# testv1.net
KiCad netlist of a schematic drawn in EAGLE
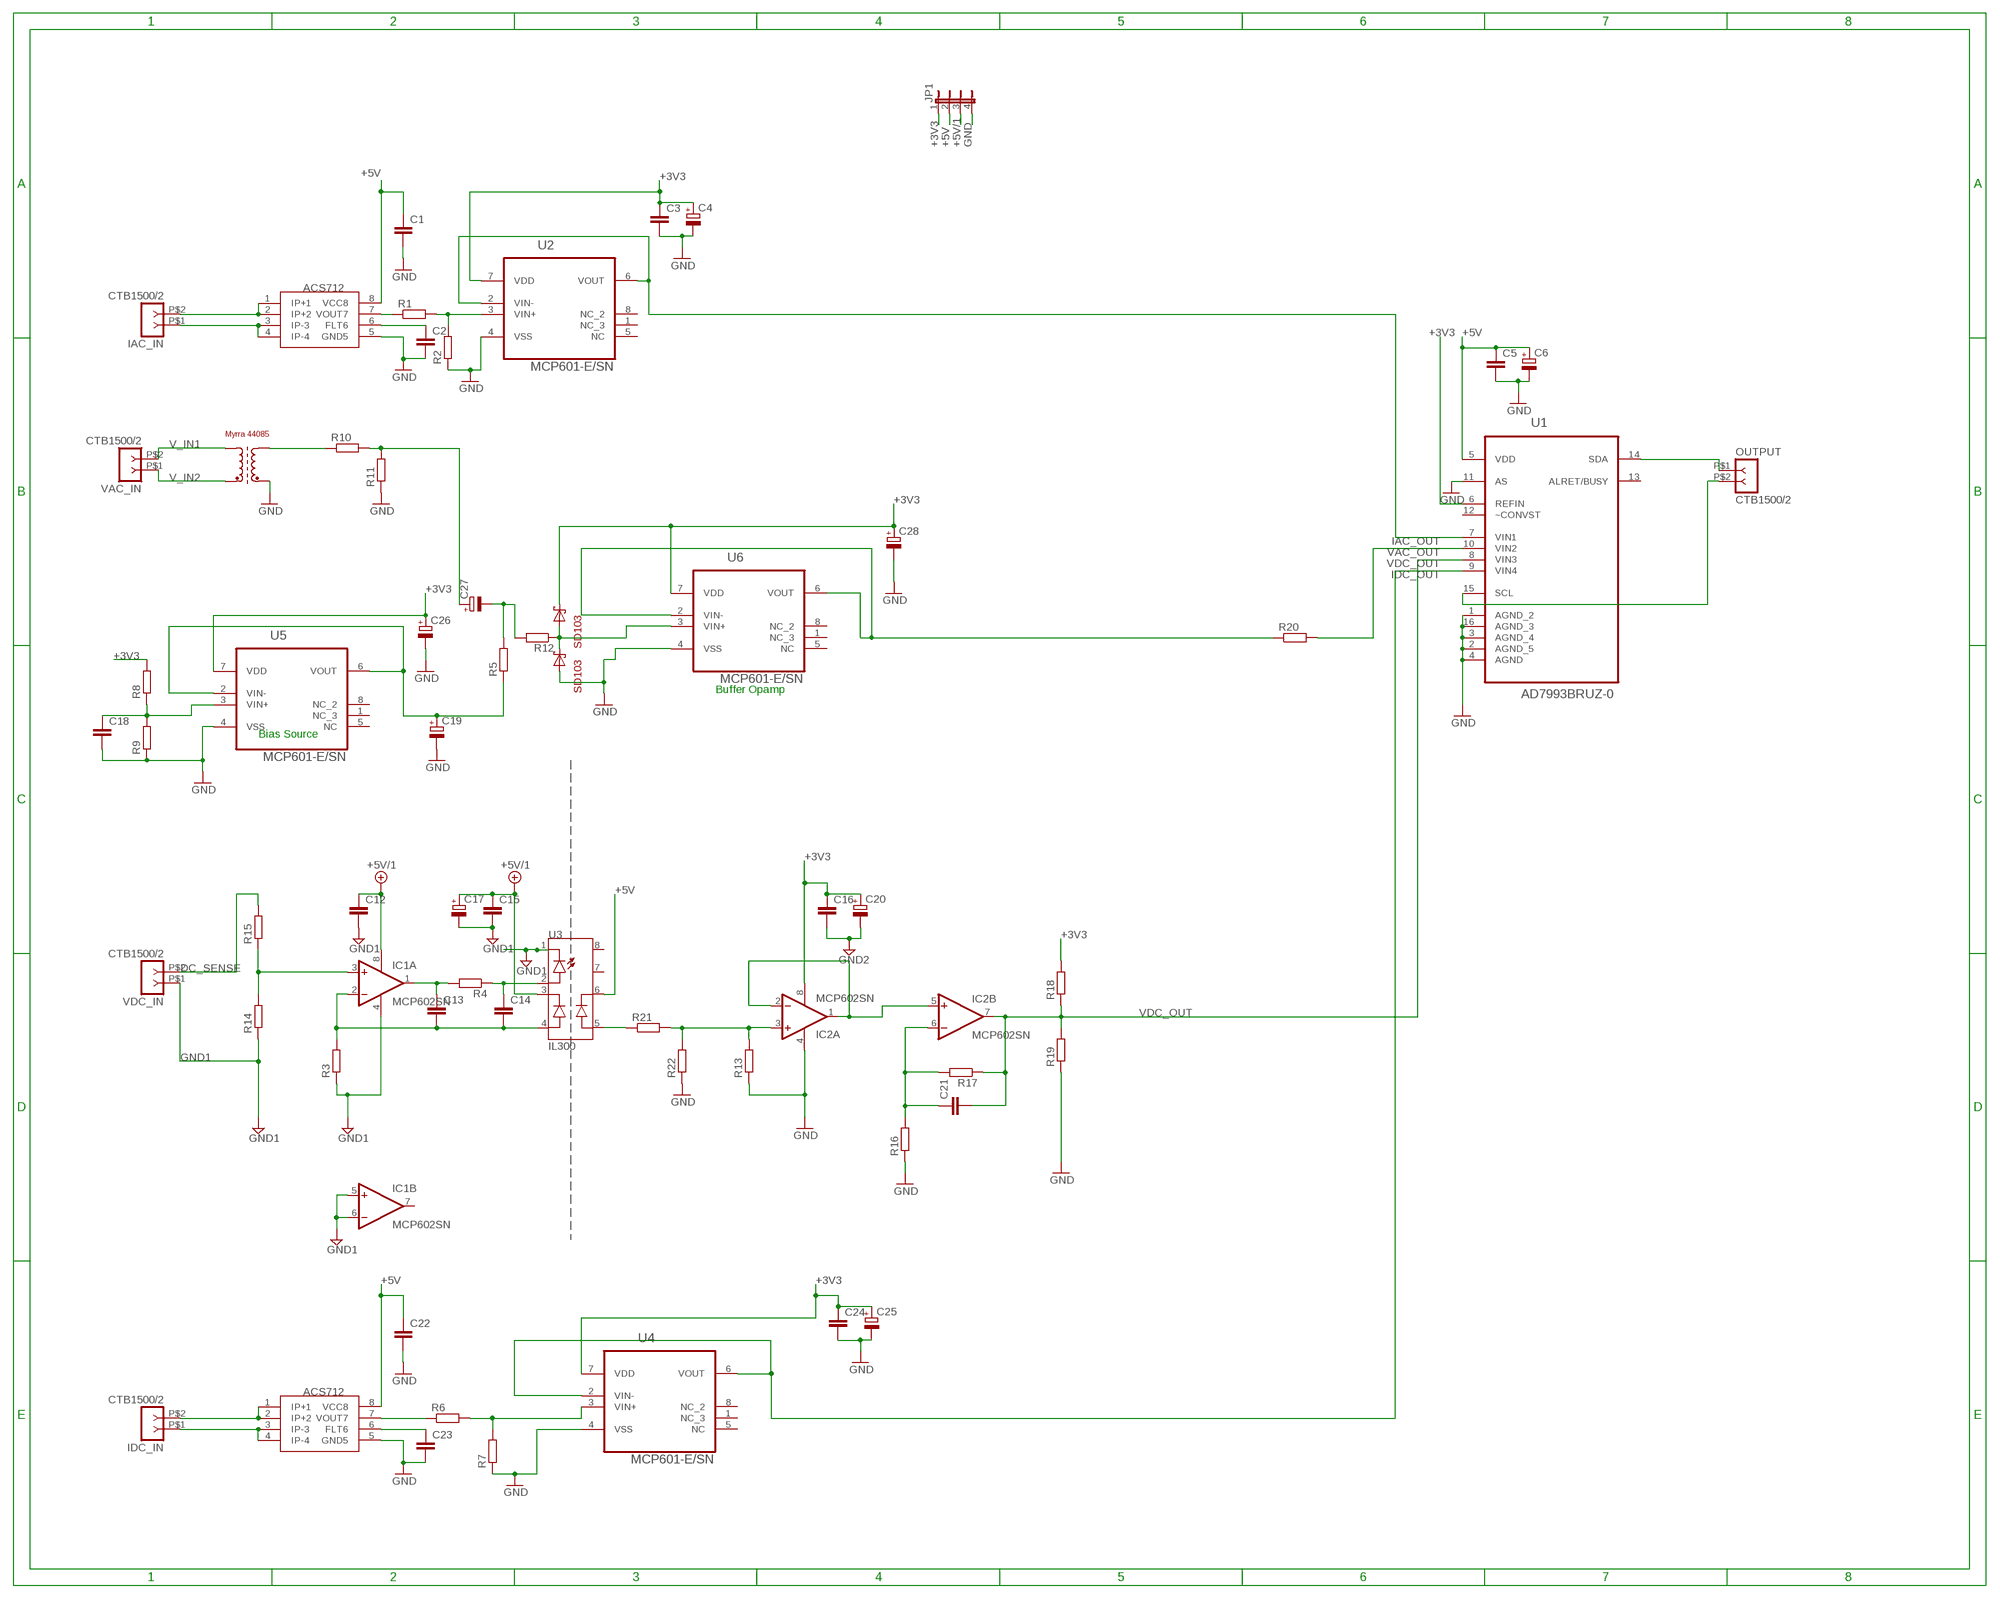
[diagram p0: schematic, sheet 1]

(export (version "E")
  (design (tool "Eeschema 10.0.6"))
  (components
    (comp (ref "C1")
      (value "C-EU025-025X050")
      (footprint "eagle-import:C025-025X050")
      (libsource (lib "eagle-import") (part "C-EU025-025X050"))
    )
    (comp (ref "C2")
      (value "C-EU025-025X050")
      (footprint "eagle-import:C025-025X050")
      (libsource (lib "eagle-import") (part "C-EU025-025X050"))
    )
    (comp (ref "C3")
      (value "C-EU025-025X050")
      (footprint "eagle-import:C025-025X050")
      (libsource (lib "eagle-import") (part "C-EU025-025X050"))
    )
    (comp (ref "C4")
      (value "CPOL-EUE2-4")
      (footprint "eagle-import:E2-4")
      (libsource (lib "eagle-import") (part "CPOL-EUE2-4"))
    )
    (comp (ref "C5")
      (value "C-EU025-025X050")
      (footprint "eagle-import:C025-025X050")
      (libsource (lib "eagle-import") (part "C-EU025-025X050"))
    )
    (comp (ref "C6")
      (value "CPOL-EUE2-4")
      (footprint "eagle-import:E2-4")
      (libsource (lib "eagle-import") (part "CPOL-EUE2-4"))
    )
    (comp (ref "C12")
      (value "C-EU025-025X050")
      (footprint "eagle-import:C025-025X050")
      (libsource (lib "eagle-import") (part "C-EU025-025X050"))
    )
    (comp (ref "C13")
      (value "C-EU025-025X050")
      (footprint "eagle-import:C025-025X050")
      (libsource (lib "eagle-import") (part "C-EU025-025X050"))
    )
    (comp (ref "C14")
      (value "C-EU025-025X050")
      (footprint "eagle-import:C025-025X050")
      (libsource (lib "eagle-import") (part "C-EU025-025X050"))
    )
    (comp (ref "C15")
      (value "C-EU025-025X050")
      (footprint "eagle-import:C025-025X050")
      (libsource (lib "eagle-import") (part "C-EU025-025X050"))
    )
    (comp (ref "C16")
      (value "C-EU025-025X050")
      (footprint "eagle-import:C025-025X050")
      (libsource (lib "eagle-import") (part "C-EU025-025X050"))
    )
    (comp (ref "C17")
      (value "CPOL-EUE2-4")
      (footprint "eagle-import:E2-4")
      (libsource (lib "eagle-import") (part "CPOL-EUE2-4"))
    )
    (comp (ref "C18")
      (value "C-EU025-025X050")
      (footprint "eagle-import:C025-025X050")
      (libsource (lib "eagle-import") (part "C-EU025-025X050"))
    )
    (comp (ref "C19")
      (value "CPOL-EUE2-4")
      (footprint "eagle-import:E2-4")
      (libsource (lib "eagle-import") (part "CPOL-EUE2-4"))
    )
    (comp (ref "C20")
      (value "CPOL-EUE2-4")
      (footprint "eagle-import:E2-4")
      (libsource (lib "eagle-import") (part "CPOL-EUE2-4"))
    )
    (comp (ref "C21")
      (value "C-EU025-025X050")
      (footprint "eagle-import:C025-025X050")
      (libsource (lib "eagle-import") (part "C-EU025-025X050"))
    )
    (comp (ref "C22")
      (value "C-EU025-025X050")
      (footprint "eagle-import:C025-025X050")
      (libsource (lib "eagle-import") (part "C-EU025-025X050"))
    )
    (comp (ref "C23")
      (value "C-EU025-025X050")
      (footprint "eagle-import:C025-025X050")
      (libsource (lib "eagle-import") (part "C-EU025-025X050"))
    )
    (comp (ref "C24")
      (value "C-EU025-025X050")
      (footprint "eagle-import:C025-025X050")
      (libsource (lib "eagle-import") (part "C-EU025-025X050"))
    )
    (comp (ref "C25")
      (value "CPOL-EUE2-4")
      (footprint "eagle-import:E2-4")
      (libsource (lib "eagle-import") (part "CPOL-EUE2-4"))
    )
    (comp (ref "C26")
      (value "CPOL-EUE2-4")
      (footprint "eagle-import:E2-4")
      (libsource (lib "eagle-import") (part "CPOL-EUE2-4"))
    )
    (comp (ref "C27")
      (value "CPOL-EUE2-4")
      (footprint "eagle-import:E2-4")
      (libsource (lib "eagle-import") (part "CPOL-EUE2-4"))
    )
    (comp (ref "C28")
      (value "CPOL-EUE2-4")
      (footprint "eagle-import:E2-4")
      (libsource (lib "eagle-import") (part "CPOL-EUE2-4"))
    )
    (comp (ref "IAC_IN")
      (value "CTB1500/2")
      (footprint "eagle-import:CTB1500-2")
      (libsource (lib "eagle-import") (part "CTB1500/2"))
    )
    (comp (ref "IC1")
      (value "MCP602SN")
      (footprint "eagle-import:SO08")
      (libsource (lib "eagle-import") (part "MCP602SN"))
    )
    (comp (ref "IC2")
      (value "MCP602SN")
      (footprint "eagle-import:SO08")
      (libsource (lib "eagle-import") (part "MCP602SN"))
    )
    (comp (ref "IDC_IN")
      (value "CTB1500/2")
      (footprint "eagle-import:CTB1500-2")
      (libsource (lib "eagle-import") (part "CTB1500/2"))
    )
    (comp (ref "JP1")
      (value "JP4E")
      (footprint "eagle-import:JP4")
      (libsource (lib "eagle-import") (part "JP4E"))
    )
    (comp (ref "OUTPUT")
      (value "CTB1500/2")
      (footprint "eagle-import:CTB1500-2")
      (libsource (lib "eagle-import") (part "CTB1500/2"))
    )
    (comp (ref "R1")
      (value "R-EU_0207/7")
      (footprint "eagle-import:0207_7")
      (libsource (lib "eagle-import") (part "R-EU_0207/7"))
    )
    (comp (ref "R2")
      (value "R-EU_0207/7")
      (footprint "eagle-import:0207_7")
      (libsource (lib "eagle-import") (part "R-EU_0207/7"))
    )
    (comp (ref "R3")
      (value "R-EU_0207/7")
      (footprint "eagle-import:0207_7")
      (libsource (lib "eagle-import") (part "R-EU_0207/7"))
    )
    (comp (ref "R4")
      (value "R-EU_0207/7")
      (footprint "eagle-import:0207_7")
      (libsource (lib "eagle-import") (part "R-EU_0207/7"))
    )
    (comp (ref "R5")
      (value "R-EU_0207/7")
      (footprint "eagle-import:0207_7")
      (libsource (lib "eagle-import") (part "R-EU_0207/7"))
    )
    (comp (ref "R6")
      (value "R-EU_0207/7")
      (footprint "eagle-import:0207_7")
      (libsource (lib "eagle-import") (part "R-EU_0207/7"))
    )
    (comp (ref "R7")
      (value "R-EU_0207/7")
      (footprint "eagle-import:0207_7")
      (libsource (lib "eagle-import") (part "R-EU_0207/7"))
    )
    (comp (ref "R8")
      (value "R-EU_0207/7")
      (footprint "eagle-import:0207_7")
      (libsource (lib "eagle-import") (part "R-EU_0207/7"))
    )
    (comp (ref "R9")
      (value "R-EU_0207/7")
      (footprint "eagle-import:0207_7")
      (libsource (lib "eagle-import") (part "R-EU_0207/7"))
    )
    (comp (ref "R10")
      (value "R-EU_0207/7")
      (footprint "eagle-import:0207_7")
      (libsource (lib "eagle-import") (part "R-EU_0207/7"))
    )
    (comp (ref "R11")
      (value "R-EU_0207/7")
      (footprint "eagle-import:0207_7")
      (libsource (lib "eagle-import") (part "R-EU_0207/7"))
    )
    (comp (ref "R12")
      (value "R-EU_0207/7")
      (footprint "eagle-import:0207_7")
      (libsource (lib "eagle-import") (part "R-EU_0207/7"))
    )
    (comp (ref "R13")
      (value "R-EU_0207/7")
      (footprint "eagle-import:0207_7")
      (libsource (lib "eagle-import") (part "R-EU_0207/7"))
    )
    (comp (ref "R14")
      (value "R-EU_0207/7")
      (footprint "eagle-import:0207_7")
      (libsource (lib "eagle-import") (part "R-EU_0207/7"))
    )
    (comp (ref "R15")
      (value "R-EU_0207/7")
      (footprint "eagle-import:0207_7")
      (libsource (lib "eagle-import") (part "R-EU_0207/7"))
    )
    (comp (ref "R16")
      (value "R-EU_0207/7")
      (footprint "eagle-import:0207_7")
      (libsource (lib "eagle-import") (part "R-EU_0207/7"))
    )
    (comp (ref "R17")
      (value "R-EU_0207/7")
      (footprint "eagle-import:0207_7")
      (libsource (lib "eagle-import") (part "R-EU_0207/7"))
    )
    (comp (ref "R18")
      (value "R-EU_0207/7")
      (footprint "eagle-import:0207_7")
      (libsource (lib "eagle-import") (part "R-EU_0207/7"))
    )
    (comp (ref "R19")
      (value "R-EU_0207/7")
      (footprint "eagle-import:0207_7")
      (libsource (lib "eagle-import") (part "R-EU_0207/7"))
    )
    (comp (ref "R20")
      (value "R-EU_0207/7")
      (footprint "eagle-import:0207_7")
      (libsource (lib "eagle-import") (part "R-EU_0207/7"))
    )
    (comp (ref "R21")
      (value "R-EU_0207/7")
      (footprint "eagle-import:0207_7")
      (libsource (lib "eagle-import") (part "R-EU_0207/7"))
    )
    (comp (ref "R22")
      (value "R-EU_0207/7")
      (footprint "eagle-import:0207_7")
      (libsource (lib "eagle-import") (part "R-EU_0207/7"))
    )
    (comp (ref "U$1")
      (value "ACS712")
      (footprint "eagle-import:SOIC8")
      (libsource (lib "eagle-import") (part "ACS712"))
    )
    (comp (ref "U$6")
      (value "MYRRA_4408")
      (footprint "eagle-import:4408")
      (libsource (lib "eagle-import") (part "MYRRA_4408"))
    )
    (comp (ref "U$7")
      (value "SD103A")
      (footprint "eagle-import:D035-10")
      (libsource (lib "eagle-import") (part "SD103A"))
    )
    (comp (ref "U$8")
      (value "SD103A")
      (footprint "eagle-import:D035-10")
      (libsource (lib "eagle-import") (part "SD103A"))
    )
    (comp (ref "U$10")
      (value "ACS712")
      (footprint "eagle-import:SOIC8")
      (libsource (lib "eagle-import") (part "ACS712"))
    )
    (comp (ref "U1")
      (value "AD7993BRUZ-0")
      (footprint "eagle-import:SOP65P640X120-16N")
      (libsource (lib "eagle-import") (part "AD7993BRUZ-0"))
    )
    (comp (ref "U2")
      (value "MCP601-E/SN")
      (footprint "eagle-import:SOIC127P600X175-8N")
      (libsource (lib "eagle-import") (part "MCP601-E/SN"))
    )
    (comp (ref "U3")
      (value "IL300")
      (footprint "eagle-import:SO8")
      (libsource (lib "eagle-import") (part "IL300"))
    )
    (comp (ref "U4")
      (value "MCP601-E/SN")
      (footprint "eagle-import:SOIC127P600X175-8N")
      (libsource (lib "eagle-import") (part "MCP601-E/SN"))
    )
    (comp (ref "U5")
      (value "MCP601-E/SN")
      (footprint "eagle-import:SOIC127P600X175-8N")
      (libsource (lib "eagle-import") (part "MCP601-E/SN"))
    )
    (comp (ref "U6")
      (value "MCP601-E/SN")
      (footprint "eagle-import:SOIC127P600X175-8N")
      (libsource (lib "eagle-import") (part "MCP601-E/SN"))
    )
    (comp (ref "VAC_IN")
      (value "CTB1500/2")
      (footprint "eagle-import:CTB1500-2")
      (libsource (lib "eagle-import") (part "CTB1500/2"))
    )
    (comp (ref "VDC_IN")
      (value "CTB1500/2")
      (footprint "eagle-import:CTB1500-2")
      (libsource (lib "eagle-import") (part "CTB1500/2"))
    )
  )
  (nets
    (net (code "1") (name "+5V{slash}1") (class "Default")
      (node (ref "C12") (pin "1") (pinfunction "1_1") (pintype "passive"))
      (node (ref "C15") (pin "1") (pinfunction "1_1") (pintype "passive"))
      (node (ref "C17") (pin "+") (pinfunction "+_+") (pintype "passive"))
      (node (ref "IC1") (pin "8") (pinfunction "V+_8") (pintype "power_in"))
      (node (ref "JP1") (pin "3") (pinfunction "3_3") (pintype "passive"))
      (node (ref "U3") (pin "3") (pinfunction "C_FB_3") (pintype "passive"))
    )
    (net (code "2") (name "/+3V3") (class "Default")
      (node (ref "C16") (pin "1") (pinfunction "1_1") (pintype "passive"))
      (node (ref "C20") (pin "+") (pinfunction "+_+") (pintype "passive"))
      (node (ref "C24") (pin "1") (pinfunction "1_1") (pintype "passive"))
      (node (ref "C25") (pin "+") (pinfunction "+_+") (pintype "passive"))
      (node (ref "C26") (pin "+") (pinfunction "+_+") (pintype "passive"))
      (node (ref "C28") (pin "+") (pinfunction "+_+") (pintype "passive"))
      (node (ref "C3") (pin "1") (pinfunction "1_1") (pintype "passive"))
      (node (ref "C4") (pin "+") (pinfunction "+_+") (pintype "passive"))
      (node (ref "IC2") (pin "8") (pinfunction "V+_8") (pintype "power_in"))
      (node (ref "JP1") (pin "1") (pinfunction "1_1") (pintype "passive"))
      (node (ref "R18") (pin "2") (pinfunction "2_2") (pintype "passive"))
      (node (ref "R8") (pin "2") (pinfunction "2_2") (pintype "passive"))
      (node (ref "U$7") (pin "C") (pinfunction "C_C") (pintype "passive"))
      (node (ref "U1") (pin "6") (pinfunction "REFIN_6") (pintype "input"))
      (node (ref "U2") (pin "7") (pinfunction "VDD_7") (pintype "power_in"))
      (node (ref "U4") (pin "7") (pinfunction "VDD_7") (pintype "power_in"))
      (node (ref "U5") (pin "7") (pinfunction "VDD_7") (pintype "power_in"))
      (node (ref "U6") (pin "7") (pinfunction "VDD_7") (pintype "power_in"))
    )
    (net (code "3") (name "/+5V") (class "Default")
      (node (ref "C1") (pin "1") (pinfunction "1_1") (pintype "passive"))
      (node (ref "C22") (pin "1") (pinfunction "1_1") (pintype "passive"))
      (node (ref "C5") (pin "1") (pinfunction "1_1") (pintype "passive"))
      (node (ref "C6") (pin "+") (pinfunction "+_+") (pintype "passive"))
      (node (ref "JP1") (pin "2") (pinfunction "2_2") (pintype "passive"))
      (node (ref "U$1") (pin "8") (pinfunction "VCC8_8") (pintype "power_in"))
      (node (ref "U$10") (pin "8") (pinfunction "VCC8_8") (pintype "power_in"))
      (node (ref "U1") (pin "5") (pinfunction "VDD_5") (pintype "power_in"))
      (node (ref "U3") (pin "6") (pinfunction "C_OUT_6") (pintype "passive"))
    )
    (net (code "4") (name "/DC_SENSE") (class "Default")
      (node (ref "R15") (pin "2") (pinfunction "2_2") (pintype "passive"))
      (node (ref "VDC_IN") (pin "P$2") (pinfunction "2_P$2") (pintype "passive"))
    )
    (net (code "5") (name "/IAC_OUT") (class "Default")
      (node (ref "U1") (pin "7") (pinfunction "VIN1_7") (pintype "input"))
      (node (ref "U2") (pin "2") (pinfunction "VIN-_2") (pintype "input"))
      (node (ref "U2") (pin "6") (pinfunction "VOUT_6") (pintype "output"))
    )
    (net (code "6") (name "/IDC_OUT") (class "Default")
      (node (ref "U1") (pin "9") (pinfunction "VIN4_9") (pintype "input"))
      (node (ref "U4") (pin "2") (pinfunction "VIN-_2") (pintype "input"))
      (node (ref "U4") (pin "6") (pinfunction "VOUT_6") (pintype "output"))
    )
    (net (code "7") (name "/VAC_OUT") (class "Default")
      (node (ref "R20") (pin "2") (pinfunction "2_2") (pintype "passive"))
      (node (ref "U1") (pin "10") (pinfunction "VIN2_10") (pintype "input"))
    )
    (net (code "8") (name "/VDC_OUT") (class "Default")
      (node (ref "C21") (pin "2") (pinfunction "2_2") (pintype "passive"))
      (node (ref "IC2") (pin "7") (pinfunction "OUT_7") (pintype "output"))
      (node (ref "R17") (pin "1") (pinfunction "1_1") (pintype "passive"))
      (node (ref "R18") (pin "1") (pinfunction "1_1") (pintype "passive"))
      (node (ref "R19") (pin "2") (pinfunction "2_2") (pintype "passive"))
      (node (ref "U1") (pin "8") (pinfunction "VIN3_8") (pintype "input"))
    )
    (net (code "9") (name "/V_IN1") (class "Default")
      (node (ref "U$6") (pin "PIN5") (pinfunction "A1_PIN5") (pintype "passive"))
      (node (ref "VAC_IN") (pin "P$2") (pinfunction "2_P$2") (pintype "passive"))
    )
    (net (code "10") (name "/V_IN2") (class "Default")
      (node (ref "U$6") (pin "PIN1") (pinfunction "E1_PIN1") (pintype "passive"))
      (node (ref "VAC_IN") (pin "P$1") (pinfunction "1_P$1") (pintype "passive"))
    )
    (net (code "11") (name "GND") (class "Default")
      (node (ref "C1") (pin "2") (pinfunction "2_2") (pintype "passive"))
      (node (ref "C18") (pin "2") (pinfunction "2_2") (pintype "passive"))
      (node (ref "C19") (pin "-") (pinfunction "-_-") (pintype "passive"))
      (node (ref "C2") (pin "2") (pinfunction "2_2") (pintype "passive"))
      (node (ref "C22") (pin "2") (pinfunction "2_2") (pintype "passive"))
      (node (ref "C23") (pin "2") (pinfunction "2_2") (pintype "passive"))
      (node (ref "C24") (pin "2") (pinfunction "2_2") (pintype "passive"))
      (node (ref "C25") (pin "-") (pinfunction "-_-") (pintype "passive"))
      (node (ref "C26") (pin "-") (pinfunction "-_-") (pintype "passive"))
      (node (ref "C28") (pin "-") (pinfunction "-_-") (pintype "passive"))
      (node (ref "C3") (pin "2") (pinfunction "2_2") (pintype "passive"))
      (node (ref "C4") (pin "-") (pinfunction "-_-") (pintype "passive"))
      (node (ref "C5") (pin "2") (pinfunction "2_2") (pintype "passive"))
      (node (ref "C6") (pin "-") (pinfunction "-_-") (pintype "passive"))
      (node (ref "IC2") (pin "4") (pinfunction "V-_4") (pintype "power_in"))
      (node (ref "JP1") (pin "4") (pinfunction "4_4") (pintype "passive"))
      (node (ref "R11") (pin "1") (pinfunction "1_1") (pintype "passive"))
      (node (ref "R13") (pin "1") (pinfunction "1_1") (pintype "passive"))
      (node (ref "R16") (pin "1") (pinfunction "1_1") (pintype "passive"))
      (node (ref "R19") (pin "1") (pinfunction "1_1") (pintype "passive"))
      (node (ref "R2") (pin "1") (pinfunction "1_1") (pintype "passive"))
      (node (ref "R22") (pin "1") (pinfunction "1_1") (pintype "passive"))
      (node (ref "R7") (pin "1") (pinfunction "1_1") (pintype "passive"))
      (node (ref "R9") (pin "1") (pinfunction "1_1") (pintype "passive"))
      (node (ref "U$1") (pin "5") (pinfunction "GND5_5") (pintype "power_in"))
      (node (ref "U$10") (pin "5") (pinfunction "GND5_5") (pintype "power_in"))
      (node (ref "U$6") (pin "PIN9") (pinfunction "E2_PIN9") (pintype "passive"))
      (node (ref "U$8") (pin "A") (pinfunction "A_A") (pintype "passive"))
      (node (ref "U1") (pin "1") (pinfunction "AGND_2_1") (pintype "passive"))
      (node (ref "U1") (pin "11") (pinfunction "AS_11") (pintype "input"))
      (node (ref "U1") (pin "16") (pinfunction "AGND_3_16") (pintype "passive"))
      (node (ref "U1") (pin "2") (pinfunction "AGND_5_2") (pintype "passive"))
      (node (ref "U1") (pin "3") (pinfunction "AGND_4_3") (pintype "passive"))
      (node (ref "U1") (pin "4") (pinfunction "AGND_4") (pintype "passive"))
      (node (ref "U2") (pin "4") (pinfunction "VSS_4") (pintype "power_in"))
      (node (ref "U4") (pin "4") (pinfunction "VSS_4") (pintype "power_in"))
      (node (ref "U5") (pin "4") (pinfunction "VSS_4") (pintype "power_in"))
      (node (ref "U6") (pin "4") (pinfunction "VSS_4") (pintype "power_in"))
    )
    (net (code "12") (name "GND1") (class "Default")
      (node (ref "C12") (pin "2") (pinfunction "2_2") (pintype "passive"))
      (node (ref "C15") (pin "2") (pinfunction "2_2") (pintype "passive"))
      (node (ref "C17") (pin "-") (pinfunction "-_-") (pintype "passive"))
      (node (ref "IC1") (pin "4") (pinfunction "V-_4") (pintype "power_in"))
      (node (ref "IC1") (pin "5") (pinfunction "+IN_5") (pintype "input"))
      (node (ref "IC1") (pin "6") (pinfunction "-IN_6") (pintype "input"))
      (node (ref "R14") (pin "1") (pinfunction "1_1") (pintype "passive"))
      (node (ref "R3") (pin "1") (pinfunction "1_1") (pintype "passive"))
      (node (ref "U3") (pin "1") (pinfunction "C_LED_1") (pintype "passive"))
      (node (ref "VDC_IN") (pin "P$1") (pinfunction "1_P$1") (pintype "passive"))
    )
    (net (code "13") (name "GND2") (class "Default")
      (node (ref "C16") (pin "2") (pinfunction "2_2") (pintype "passive"))
      (node (ref "C20") (pin "-") (pinfunction "-_-") (pintype "passive"))
    )
    (net (code "14") (name "Net-(C27-Pad+)") (class "Default")
      (node (ref "C27") (pin "+") (pinfunction "+_+") (pintype "passive"))
      (node (ref "R10") (pin "2") (pinfunction "2_2") (pintype "passive"))
      (node (ref "R11") (pin "2") (pinfunction "2_2") (pintype "passive"))
    )
    (net (code "15") (name "Net-(C27-Pad-)") (class "Default")
      (node (ref "C27") (pin "-") (pinfunction "-_-") (pintype "passive"))
      (node (ref "R12") (pin "2") (pinfunction "2_2") (pintype "passive"))
      (node (ref "R5") (pin "2") (pinfunction "2_2") (pintype "passive"))
    )
    (net (code "16") (name "Net-(IAC_IN-1)") (class "Default")
      (node (ref "IAC_IN") (pin "P$1") (pinfunction "1_P$1") (pintype "passive"))
      (node (ref "U$1") (pin "3") (pinfunction "IP-3_3") (pintype "bidirectional"))
      (node (ref "U$1") (pin "4") (pinfunction "IP-4_4") (pintype "bidirectional"))
    )
    (net (code "17") (name "Net-(IAC_IN-2)") (class "Default")
      (node (ref "IAC_IN") (pin "P$2") (pinfunction "2_P$2") (pintype "passive"))
      (node (ref "U$1") (pin "1") (pinfunction "IP+1_1") (pintype "bidirectional"))
      (node (ref "U$1") (pin "2") (pinfunction "IP+2_2") (pintype "bidirectional"))
    )
    (net (code "18") (name "Net-(IC1A-+IN)") (class "Default")
      (node (ref "IC1") (pin "3") (pinfunction "+IN_3") (pintype "input"))
      (node (ref "R14") (pin "2") (pinfunction "2_2") (pintype "passive"))
      (node (ref "R15") (pin "1") (pinfunction "1_1") (pintype "passive"))
    )
    (net (code "19") (name "Net-(IC1A--IN)") (class "Default")
      (node (ref "C13") (pin "2") (pinfunction "2_2") (pintype "passive"))
      (node (ref "C14") (pin "2") (pinfunction "2_2") (pintype "passive"))
      (node (ref "IC1") (pin "2") (pinfunction "-IN_2") (pintype "input"))
      (node (ref "R3") (pin "2") (pinfunction "2_2") (pintype "passive"))
      (node (ref "U3") (pin "4") (pinfunction "A_FB_4") (pintype "passive"))
    )
    (net (code "20") (name "Net-(IC1A-OUT)") (class "Default")
      (node (ref "C13") (pin "1") (pinfunction "1_1") (pintype "passive"))
      (node (ref "IC1") (pin "1") (pinfunction "OUT_1") (pintype "output"))
      (node (ref "R4") (pin "2") (pinfunction "2_2") (pintype "passive"))
    )
    (net (code "21") (name "Net-(IC2A-+IN)") (class "Default")
      (node (ref "IC2") (pin "3") (pinfunction "+IN_3") (pintype "input"))
      (node (ref "R13") (pin "2") (pinfunction "2_2") (pintype "passive"))
      (node (ref "R21") (pin "2") (pinfunction "2_2") (pintype "passive"))
      (node (ref "R22") (pin "2") (pinfunction "2_2") (pintype "passive"))
    )
    (net (code "22") (name "Net-(IC2A--IN)") (class "Default")
      (node (ref "IC2") (pin "1") (pinfunction "OUT_1") (pintype "output"))
      (node (ref "IC2") (pin "2") (pinfunction "-IN_2") (pintype "input"))
      (node (ref "IC2") (pin "5") (pinfunction "+IN_5") (pintype "input"))
    )
    (net (code "23") (name "Net-(IC2B--IN)") (class "Default")
      (node (ref "C21") (pin "1") (pinfunction "1_1") (pintype "passive"))
      (node (ref "IC2") (pin "6") (pinfunction "-IN_6") (pintype "input"))
      (node (ref "R16") (pin "2") (pinfunction "2_2") (pintype "passive"))
      (node (ref "R17") (pin "2") (pinfunction "2_2") (pintype "passive"))
    )
    (net (code "24") (name "Net-(IDC_IN-1)") (class "Default")
      (node (ref "IDC_IN") (pin "P$1") (pinfunction "1_P$1") (pintype "passive"))
      (node (ref "U$10") (pin "3") (pinfunction "IP-3_3") (pintype "bidirectional"))
      (node (ref "U$10") (pin "4") (pinfunction "IP-4_4") (pintype "bidirectional"))
    )
    (net (code "25") (name "Net-(IDC_IN-2)") (class "Default")
      (node (ref "IDC_IN") (pin "P$2") (pinfunction "2_P$2") (pintype "passive"))
      (node (ref "U$10") (pin "1") (pinfunction "IP+1_1") (pintype "bidirectional"))
      (node (ref "U$10") (pin "2") (pinfunction "IP+2_2") (pintype "bidirectional"))
    )
    (net (code "26") (name "Net-(OUTPUT-1)") (class "Default")
      (node (ref "OUTPUT") (pin "P$1") (pinfunction "1_P$1") (pintype "passive"))
      (node (ref "U1") (pin "14") (pinfunction "SDA_14") (pintype "bidirectional"))
    )
    (net (code "27") (name "Net-(OUTPUT-2)") (class "Default")
      (node (ref "OUTPUT") (pin "P$2") (pinfunction "2_P$2") (pintype "passive"))
      (node (ref "U1") (pin "15") (pinfunction "SCL_15") (pintype "input"))
    )
    (net (code "28") (name "Net-(U$1-FLT6)") (class "Default")
      (node (ref "C2") (pin "1") (pinfunction "1_1") (pintype "passive"))
      (node (ref "U$1") (pin "6") (pinfunction "FLT6_6") (pintype "passive"))
    )
    (net (code "29") (name "Net-(U$1-VOUT7)") (class "Default")
      (node (ref "R1") (pin "1") (pinfunction "1_1") (pintype "passive"))
      (node (ref "U$1") (pin "7") (pinfunction "VOUT7_7") (pintype "output"))
    )
    (net (code "30") (name "Net-(U$6-A2)") (class "Default")
      (node (ref "R10") (pin "1") (pinfunction "1_1") (pintype "passive"))
      (node (ref "U$6") (pin "PIN7") (pinfunction "A2_PIN7") (pintype "passive"))
    )
    (net (code "31") (name "Net-(U$10-FLT6)") (class "Default")
      (node (ref "C23") (pin "1") (pinfunction "1_1") (pintype "passive"))
      (node (ref "U$10") (pin "6") (pinfunction "FLT6_6") (pintype "passive"))
    )
    (net (code "32") (name "Net-(U$10-VOUT7)") (class "Default")
      (node (ref "R6") (pin "1") (pinfunction "1_1") (pintype "passive"))
      (node (ref "U$10") (pin "7") (pinfunction "VOUT7_7") (pintype "output"))
    )
    (net (code "33") (name "Net-(U2-VIN+)") (class "Default")
      (node (ref "R1") (pin "2") (pinfunction "2_2") (pintype "passive"))
      (node (ref "R2") (pin "2") (pinfunction "2_2") (pintype "passive"))
      (node (ref "U2") (pin "3") (pinfunction "VIN+_3") (pintype "input"))
    )
    (net (code "34") (name "Net-(U3-A_LED)") (class "Default")
      (node (ref "C14") (pin "1") (pinfunction "1_1") (pintype "passive"))
      (node (ref "R4") (pin "1") (pinfunction "1_1") (pintype "passive"))
      (node (ref "U3") (pin "2") (pinfunction "A_LED_2") (pintype "passive"))
    )
    (net (code "35") (name "Net-(U3-A_OUT)") (class "Default")
      (node (ref "R21") (pin "1") (pinfunction "1_1") (pintype "passive"))
      (node (ref "U3") (pin "5") (pinfunction "A_OUT_5") (pintype "passive"))
    )
    (net (code "36") (name "Net-(U4-VIN+)") (class "Default")
      (node (ref "R6") (pin "2") (pinfunction "2_2") (pintype "passive"))
      (node (ref "R7") (pin "2") (pinfunction "2_2") (pintype "passive"))
      (node (ref "U4") (pin "3") (pinfunction "VIN+_3") (pintype "input"))
    )
    (net (code "37") (name "Net-(U5-VIN+)") (class "Default")
      (node (ref "C18") (pin "1") (pinfunction "1_1") (pintype "passive"))
      (node (ref "R8") (pin "1") (pinfunction "1_1") (pintype "passive"))
      (node (ref "R9") (pin "2") (pinfunction "2_2") (pintype "passive"))
      (node (ref "U5") (pin "3") (pinfunction "VIN+_3") (pintype "input"))
    )
    (net (code "38") (name "Net-(U5-VIN-)") (class "Default")
      (node (ref "C19") (pin "+") (pinfunction "+_+") (pintype "passive"))
      (node (ref "R5") (pin "1") (pinfunction "1_1") (pintype "passive"))
      (node (ref "U5") (pin "2") (pinfunction "VIN-_2") (pintype "input"))
      (node (ref "U5") (pin "6") (pinfunction "VOUT_6") (pintype "output"))
    )
    (net (code "39") (name "Net-(U6-VIN+)") (class "Default")
      (node (ref "R12") (pin "1") (pinfunction "1_1") (pintype "passive"))
      (node (ref "U$7") (pin "A") (pinfunction "A_A") (pintype "passive"))
      (node (ref "U$8") (pin "C") (pinfunction "C_C") (pintype "passive"))
      (node (ref "U6") (pin "3") (pinfunction "VIN+_3") (pintype "input"))
    )
    (net (code "40") (name "Net-(U6-VIN-)") (class "Default")
      (node (ref "R20") (pin "1") (pinfunction "1_1") (pintype "passive"))
      (node (ref "U6") (pin "2") (pinfunction "VIN-_2") (pintype "input"))
      (node (ref "U6") (pin "6") (pinfunction "VOUT_6") (pintype "output"))
    )
    (net (code "41") (name "unconnected-(IC1B-OUT-Pad7)") (class "Default")
      (node (ref "IC1") (pin "7") (pinfunction "OUT_7") (pintype "output"))
    )
    (net (code "42") (name "unconnected-(U1-ALRET{slash}BUSY-Pad13)") (class "Default")
      (node (ref "U1") (pin "13") (pinfunction "ALRET/BUSY_13") (pintype "output"))
    )
    (net (code "43") (name "unconnected-(U1-~{CONVST}-Pad12)") (class "Default")
      (node (ref "U1") (pin "12") (pinfunction "~{CONVST}_12") (pintype "input"))
    )
    (net (code "44") (name "unconnected-(U2-NC-Pad5)") (class "Default")
      (node (ref "U2") (pin "5") (pinfunction "NC_5") (pintype "no_connect"))
    )
    (net (code "45") (name "unconnected-(U2-NC_2-Pad8)") (class "Default")
      (node (ref "U2") (pin "8") (pinfunction "NC_2_8") (pintype "no_connect"))
    )
    (net (code "46") (name "unconnected-(U2-NC_3-Pad1)") (class "Default")
      (node (ref "U2") (pin "1") (pinfunction "NC_3_1") (pintype "no_connect"))
    )
    (net (code "47") (name "unconnected-(U3-PIN7-Pad7)") (class "Default")
      (node (ref "U3") (pin "7") (pinfunction "PIN7_7") (pintype "no_connect"))
    )
    (net (code "48") (name "unconnected-(U3-PIN8-Pad8)") (class "Default")
      (node (ref "U3") (pin "8") (pinfunction "PIN8_8") (pintype "no_connect"))
    )
    (net (code "49") (name "unconnected-(U4-NC-Pad5)") (class "Default")
      (node (ref "U4") (pin "5") (pinfunction "NC_5") (pintype "no_connect"))
    )
    (net (code "50") (name "unconnected-(U4-NC_2-Pad8)") (class "Default")
      (node (ref "U4") (pin "8") (pinfunction "NC_2_8") (pintype "no_connect"))
    )
    (net (code "51") (name "unconnected-(U4-NC_3-Pad1)") (class "Default")
      (node (ref "U4") (pin "1") (pinfunction "NC_3_1") (pintype "no_connect"))
    )
    (net (code "52") (name "unconnected-(U5-NC-Pad5)") (class "Default")
      (node (ref "U5") (pin "5") (pinfunction "NC_5") (pintype "no_connect"))
    )
    (net (code "53") (name "unconnected-(U5-NC_2-Pad8)") (class "Default")
      (node (ref "U5") (pin "8") (pinfunction "NC_2_8") (pintype "no_connect"))
    )
    (net (code "54") (name "unconnected-(U5-NC_3-Pad1)") (class "Default")
      (node (ref "U5") (pin "1") (pinfunction "NC_3_1") (pintype "no_connect"))
    )
    (net (code "55") (name "unconnected-(U6-NC-Pad5)") (class "Default")
      (node (ref "U6") (pin "5") (pinfunction "NC_5") (pintype "no_connect"))
    )
    (net (code "56") (name "unconnected-(U6-NC_2-Pad8)") (class "Default")
      (node (ref "U6") (pin "8") (pinfunction "NC_2_8") (pintype "no_connect"))
    )
    (net (code "57") (name "unconnected-(U6-NC_3-Pad1)") (class "Default")
      (node (ref "U6") (pin "1") (pinfunction "NC_3_1") (pintype "no_connect"))
    )
  )
)
